# breakout.net
KiCad netlist of a schematic drawn in EAGLE
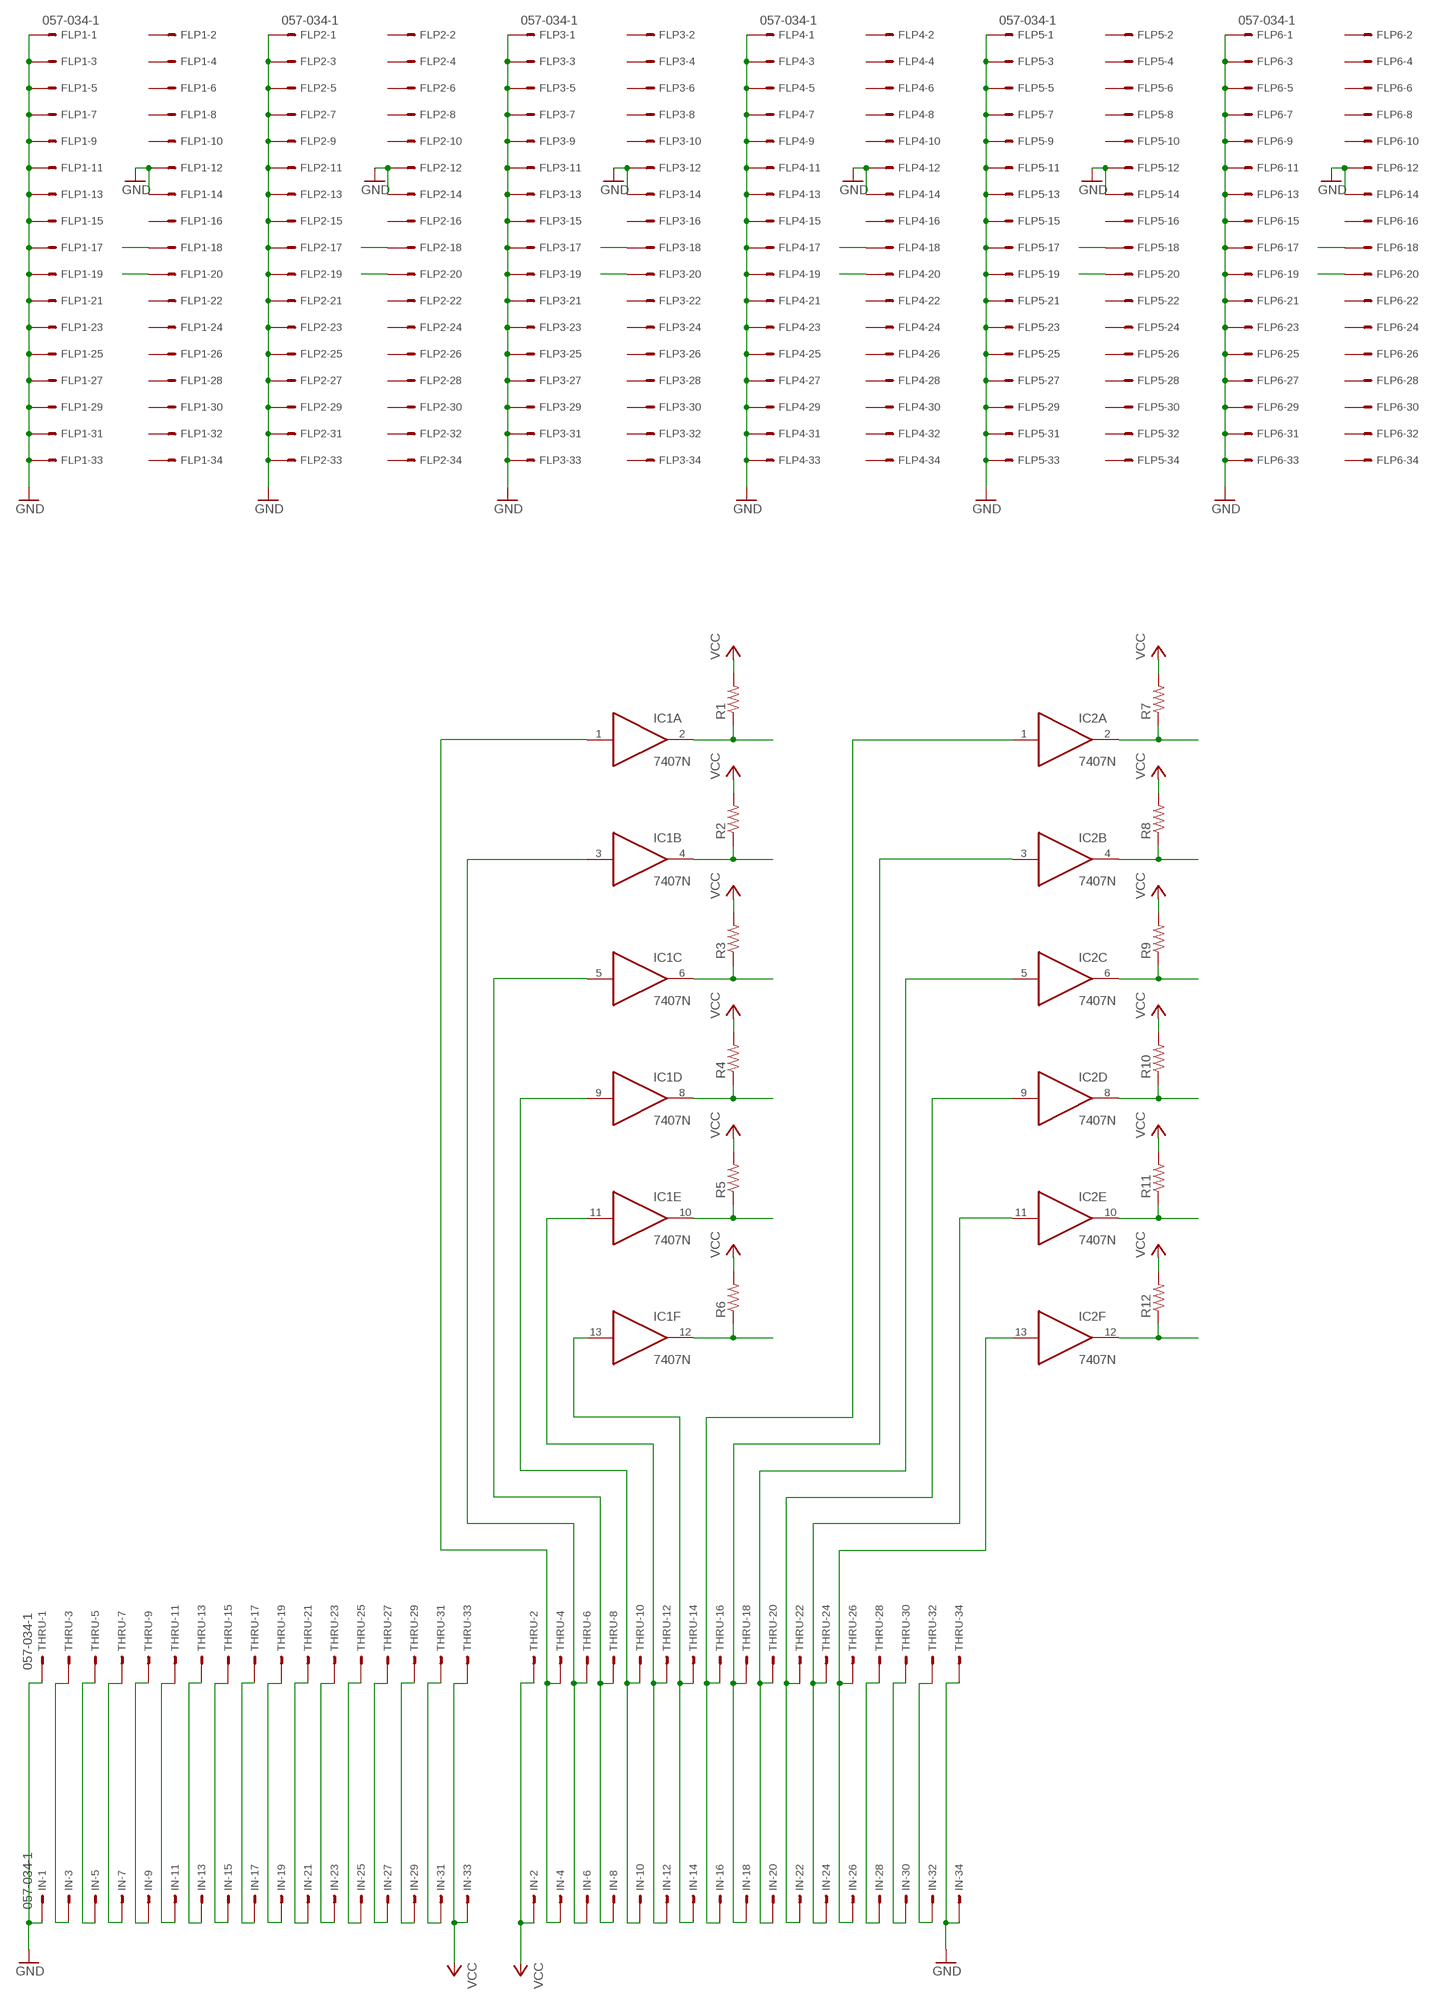
[diagram p0: schematic, sheet 1]

(export (version "E")
  (design (tool "Eeschema 10.0.6"))
  (components
    (comp (ref "FLP1")
      (value "057-034-1")
      (footprint "eagle-import:057-034-1")
      (libsource (lib "eagle-import") (part "057-034-1"))
    )
    (comp (ref "FLP2")
      (value "057-034-1")
      (footprint "eagle-import:057-034-1")
      (libsource (lib "eagle-import") (part "057-034-1"))
    )
    (comp (ref "FLP3")
      (value "057-034-1")
      (footprint "eagle-import:057-034-1")
      (libsource (lib "eagle-import") (part "057-034-1"))
    )
    (comp (ref "FLP4")
      (value "057-034-1")
      (footprint "eagle-import:057-034-1")
      (libsource (lib "eagle-import") (part "057-034-1"))
    )
    (comp (ref "FLP5")
      (value "057-034-1")
      (footprint "eagle-import:057-034-1")
      (libsource (lib "eagle-import") (part "057-034-1"))
    )
    (comp (ref "FLP6")
      (value "057-034-1")
      (footprint "eagle-import:057-034-1")
      (libsource (lib "eagle-import") (part "057-034-1"))
    )
    (comp (ref "IC1")
      (value "7407N")
      (footprint "eagle-import:DIL14")
      (libsource (lib "eagle-import") (part "7407N"))
    )
    (comp (ref "IC2")
      (value "7407N")
      (footprint "eagle-import:DIL14")
      (libsource (lib "eagle-import") (part "7407N"))
    )
    (comp (ref "IN")
      (value "057-034-1")
      (footprint "eagle-import:057-034-1")
      (libsource (lib "eagle-import") (part "057-034-1"))
    )
    (comp (ref "R1")
      (value "R-US_0204/7")
      (footprint "eagle-import:0204_7")
      (libsource (lib "eagle-import") (part "R-US_0204/7"))
    )
    (comp (ref "R2")
      (value "R-US_0204/7")
      (footprint "eagle-import:0204_7")
      (libsource (lib "eagle-import") (part "R-US_0204/7"))
    )
    (comp (ref "R3")
      (value "R-US_0204/7")
      (footprint "eagle-import:0204_7")
      (libsource (lib "eagle-import") (part "R-US_0204/7"))
    )
    (comp (ref "R4")
      (value "R-US_0204/7")
      (footprint "eagle-import:0204_7")
      (libsource (lib "eagle-import") (part "R-US_0204/7"))
    )
    (comp (ref "R5")
      (value "R-US_0204/7")
      (footprint "eagle-import:0204_7")
      (libsource (lib "eagle-import") (part "R-US_0204/7"))
    )
    (comp (ref "R6")
      (value "R-US_0204/7")
      (footprint "eagle-import:0204_7")
      (libsource (lib "eagle-import") (part "R-US_0204/7"))
    )
    (comp (ref "R7")
      (value "R-US_0204/7")
      (footprint "eagle-import:0204_7")
      (libsource (lib "eagle-import") (part "R-US_0204/7"))
    )
    (comp (ref "R8")
      (value "R-US_0204/7")
      (footprint "eagle-import:0204_7")
      (libsource (lib "eagle-import") (part "R-US_0204/7"))
    )
    (comp (ref "R9")
      (value "R-US_0204/7")
      (footprint "eagle-import:0204_7")
      (libsource (lib "eagle-import") (part "R-US_0204/7"))
    )
    (comp (ref "R10")
      (value "R-US_0204/7")
      (footprint "eagle-import:0204_7")
      (libsource (lib "eagle-import") (part "R-US_0204/7"))
    )
    (comp (ref "R11")
      (value "R-US_0204/7")
      (footprint "eagle-import:0204_7")
      (libsource (lib "eagle-import") (part "R-US_0204/7"))
    )
    (comp (ref "R12")
      (value "R-US_0204/7")
      (footprint "eagle-import:0204_7")
      (libsource (lib "eagle-import") (part "R-US_0204/7"))
    )
    (comp (ref "THRU")
      (value "057-034-1")
      (footprint "eagle-import:057-034-1")
      (libsource (lib "eagle-import") (part "057-034-1"))
    )
  )
  (nets
    (net (code "1") (name "/DIRECTION_1") (class "Default")
      (node (ref "FLP1") (pin "18") (pinfunction "S_18") (pintype "passive"))
      (node (ref "IC1") (pin "2") (pinfunction "O_2") (pintype "open_collector"))
      (node (ref "R1") (pin "1") (pinfunction "1_1") (pintype "passive"))
    )
    (net (code "2") (name "/DIRECTION_2") (class "Default")
      (node (ref "FLP2") (pin "18") (pinfunction "S_18") (pintype "passive"))
      (node (ref "IC1") (pin "6") (pinfunction "O_6") (pintype "open_collector"))
      (node (ref "R3") (pin "1") (pinfunction "1_1") (pintype "passive"))
    )
    (net (code "3") (name "/DIRECTION_3") (class "Default")
      (node (ref "FLP3") (pin "18") (pinfunction "S_18") (pintype "passive"))
      (node (ref "IC1") (pin "10") (pinfunction "O_10") (pintype "open_collector"))
      (node (ref "R5") (pin "1") (pinfunction "1_1") (pintype "passive"))
    )
    (net (code "4") (name "/DIRECTION_4") (class "Default")
      (node (ref "FLP4") (pin "18") (pinfunction "S_18") (pintype "passive"))
      (node (ref "IC2") (pin "2") (pinfunction "O_2") (pintype "open_collector"))
      (node (ref "R7") (pin "1") (pinfunction "1_1") (pintype "passive"))
    )
    (net (code "5") (name "/DIRECTION_5") (class "Default")
      (node (ref "FLP5") (pin "18") (pinfunction "S_18") (pintype "passive"))
      (node (ref "IC2") (pin "6") (pinfunction "O_6") (pintype "open_collector"))
      (node (ref "R9") (pin "1") (pinfunction "1_1") (pintype "passive"))
    )
    (net (code "6") (name "/DIRECTION_6") (class "Default")
      (node (ref "FLP6") (pin "18") (pinfunction "S_18") (pintype "passive"))
      (node (ref "IC2") (pin "10") (pinfunction "O_10") (pintype "open_collector"))
      (node (ref "R11") (pin "1") (pinfunction "1_1") (pintype "passive"))
    )
    (net (code "7") (name "/STEP_1") (class "Default")
      (node (ref "FLP1") (pin "20") (pinfunction "S_20") (pintype "passive"))
      (node (ref "IC1") (pin "4") (pinfunction "O_4") (pintype "open_collector"))
      (node (ref "R2") (pin "1") (pinfunction "1_1") (pintype "passive"))
    )
    (net (code "8") (name "/STEP_2") (class "Default")
      (node (ref "FLP2") (pin "20") (pinfunction "S_20") (pintype "passive"))
      (node (ref "IC1") (pin "8") (pinfunction "O_8") (pintype "open_collector"))
      (node (ref "R4") (pin "1") (pinfunction "1_1") (pintype "passive"))
    )
    (net (code "9") (name "/STEP_3") (class "Default")
      (node (ref "FLP3") (pin "20") (pinfunction "S_20") (pintype "passive"))
      (node (ref "IC1") (pin "12") (pinfunction "O_12") (pintype "open_collector"))
      (node (ref "R6") (pin "1") (pinfunction "1_1") (pintype "passive"))
    )
    (net (code "10") (name "/STEP_4") (class "Default")
      (node (ref "FLP4") (pin "20") (pinfunction "S_20") (pintype "passive"))
      (node (ref "IC2") (pin "4") (pinfunction "O_4") (pintype "open_collector"))
      (node (ref "R8") (pin "1") (pinfunction "1_1") (pintype "passive"))
    )
    (net (code "11") (name "/STEP_5") (class "Default")
      (node (ref "FLP5") (pin "20") (pinfunction "S_20") (pintype "passive"))
      (node (ref "IC2") (pin "8") (pinfunction "O_8") (pintype "open_collector"))
      (node (ref "R10") (pin "1") (pinfunction "1_1") (pintype "passive"))
    )
    (net (code "12") (name "/STEP_6") (class "Default")
      (node (ref "FLP6") (pin "20") (pinfunction "S_20") (pintype "passive"))
      (node (ref "IC2") (pin "12") (pinfunction "O_12") (pintype "open_collector"))
      (node (ref "R12") (pin "1") (pinfunction "1_1") (pintype "passive"))
    )
    (net (code "13") (name "GND") (class "Default")
      (node (ref "FLP1") (pin "1") (pinfunction "S_1") (pintype "passive"))
      (node (ref "FLP1") (pin "11") (pinfunction "S_11") (pintype "passive"))
      (node (ref "FLP1") (pin "12") (pinfunction "S_12") (pintype "passive"))
      (node (ref "FLP1") (pin "13") (pinfunction "S_13") (pintype "passive"))
      (node (ref "FLP1") (pin "14") (pinfunction "S_14") (pintype "passive"))
      (node (ref "FLP1") (pin "15") (pinfunction "S_15") (pintype "passive"))
      (node (ref "FLP1") (pin "17") (pinfunction "S_17") (pintype "passive"))
      (node (ref "FLP1") (pin "19") (pinfunction "S_19") (pintype "passive"))
      (node (ref "FLP1") (pin "21") (pinfunction "S_21") (pintype "passive"))
      (node (ref "FLP1") (pin "23") (pinfunction "S_23") (pintype "passive"))
      (node (ref "FLP1") (pin "25") (pinfunction "S_25") (pintype "passive"))
      (node (ref "FLP1") (pin "27") (pinfunction "S_27") (pintype "passive"))
      (node (ref "FLP1") (pin "29") (pinfunction "S_29") (pintype "passive"))
      (node (ref "FLP1") (pin "3") (pinfunction "S_3") (pintype "passive"))
      (node (ref "FLP1") (pin "31") (pinfunction "S_31") (pintype "passive"))
      (node (ref "FLP1") (pin "33") (pinfunction "S_33") (pintype "passive"))
      (node (ref "FLP1") (pin "5") (pinfunction "S_5") (pintype "passive"))
      (node (ref "FLP1") (pin "7") (pinfunction "S_7") (pintype "passive"))
      (node (ref "FLP1") (pin "9") (pinfunction "S_9") (pintype "passive"))
      (node (ref "FLP2") (pin "1") (pinfunction "S_1") (pintype "passive"))
      (node (ref "FLP2") (pin "11") (pinfunction "S_11") (pintype "passive"))
      (node (ref "FLP2") (pin "12") (pinfunction "S_12") (pintype "passive"))
      (node (ref "FLP2") (pin "13") (pinfunction "S_13") (pintype "passive"))
      (node (ref "FLP2") (pin "14") (pinfunction "S_14") (pintype "passive"))
      (node (ref "FLP2") (pin "15") (pinfunction "S_15") (pintype "passive"))
      (node (ref "FLP2") (pin "17") (pinfunction "S_17") (pintype "passive"))
      (node (ref "FLP2") (pin "19") (pinfunction "S_19") (pintype "passive"))
      (node (ref "FLP2") (pin "21") (pinfunction "S_21") (pintype "passive"))
      (node (ref "FLP2") (pin "23") (pinfunction "S_23") (pintype "passive"))
      (node (ref "FLP2") (pin "25") (pinfunction "S_25") (pintype "passive"))
      (node (ref "FLP2") (pin "27") (pinfunction "S_27") (pintype "passive"))
      (node (ref "FLP2") (pin "29") (pinfunction "S_29") (pintype "passive"))
      (node (ref "FLP2") (pin "3") (pinfunction "S_3") (pintype "passive"))
      (node (ref "FLP2") (pin "31") (pinfunction "S_31") (pintype "passive"))
      (node (ref "FLP2") (pin "33") (pinfunction "S_33") (pintype "passive"))
      (node (ref "FLP2") (pin "5") (pinfunction "S_5") (pintype "passive"))
      (node (ref "FLP2") (pin "7") (pinfunction "S_7") (pintype "passive"))
      (node (ref "FLP2") (pin "9") (pinfunction "S_9") (pintype "passive"))
      (node (ref "FLP3") (pin "1") (pinfunction "S_1") (pintype "passive"))
      (node (ref "FLP3") (pin "11") (pinfunction "S_11") (pintype "passive"))
      (node (ref "FLP3") (pin "12") (pinfunction "S_12") (pintype "passive"))
      (node (ref "FLP3") (pin "13") (pinfunction "S_13") (pintype "passive"))
      (node (ref "FLP3") (pin "14") (pinfunction "S_14") (pintype "passive"))
      (node (ref "FLP3") (pin "15") (pinfunction "S_15") (pintype "passive"))
      (node (ref "FLP3") (pin "17") (pinfunction "S_17") (pintype "passive"))
      (node (ref "FLP3") (pin "19") (pinfunction "S_19") (pintype "passive"))
      (node (ref "FLP3") (pin "21") (pinfunction "S_21") (pintype "passive"))
      (node (ref "FLP3") (pin "23") (pinfunction "S_23") (pintype "passive"))
      (node (ref "FLP3") (pin "25") (pinfunction "S_25") (pintype "passive"))
      (node (ref "FLP3") (pin "27") (pinfunction "S_27") (pintype "passive"))
      (node (ref "FLP3") (pin "29") (pinfunction "S_29") (pintype "passive"))
      (node (ref "FLP3") (pin "3") (pinfunction "S_3") (pintype "passive"))
      (node (ref "FLP3") (pin "31") (pinfunction "S_31") (pintype "passive"))
      (node (ref "FLP3") (pin "33") (pinfunction "S_33") (pintype "passive"))
      (node (ref "FLP3") (pin "5") (pinfunction "S_5") (pintype "passive"))
      (node (ref "FLP3") (pin "7") (pinfunction "S_7") (pintype "passive"))
      (node (ref "FLP3") (pin "9") (pinfunction "S_9") (pintype "passive"))
      (node (ref "FLP4") (pin "1") (pinfunction "S_1") (pintype "passive"))
      (node (ref "FLP4") (pin "11") (pinfunction "S_11") (pintype "passive"))
      (node (ref "FLP4") (pin "12") (pinfunction "S_12") (pintype "passive"))
      (node (ref "FLP4") (pin "13") (pinfunction "S_13") (pintype "passive"))
      (node (ref "FLP4") (pin "14") (pinfunction "S_14") (pintype "passive"))
      (node (ref "FLP4") (pin "15") (pinfunction "S_15") (pintype "passive"))
      (node (ref "FLP4") (pin "17") (pinfunction "S_17") (pintype "passive"))
      (node (ref "FLP4") (pin "19") (pinfunction "S_19") (pintype "passive"))
      (node (ref "FLP4") (pin "21") (pinfunction "S_21") (pintype "passive"))
      (node (ref "FLP4") (pin "23") (pinfunction "S_23") (pintype "passive"))
      (node (ref "FLP4") (pin "25") (pinfunction "S_25") (pintype "passive"))
      (node (ref "FLP4") (pin "27") (pinfunction "S_27") (pintype "passive"))
      (node (ref "FLP4") (pin "29") (pinfunction "S_29") (pintype "passive"))
      (node (ref "FLP4") (pin "3") (pinfunction "S_3") (pintype "passive"))
      (node (ref "FLP4") (pin "31") (pinfunction "S_31") (pintype "passive"))
      (node (ref "FLP4") (pin "33") (pinfunction "S_33") (pintype "passive"))
      (node (ref "FLP4") (pin "5") (pinfunction "S_5") (pintype "passive"))
      (node (ref "FLP4") (pin "7") (pinfunction "S_7") (pintype "passive"))
      (node (ref "FLP4") (pin "9") (pinfunction "S_9") (pintype "passive"))
      (node (ref "FLP5") (pin "1") (pinfunction "S_1") (pintype "passive"))
      (node (ref "FLP5") (pin "11") (pinfunction "S_11") (pintype "passive"))
      (node (ref "FLP5") (pin "12") (pinfunction "S_12") (pintype "passive"))
      (node (ref "FLP5") (pin "13") (pinfunction "S_13") (pintype "passive"))
      (node (ref "FLP5") (pin "14") (pinfunction "S_14") (pintype "passive"))
      (node (ref "FLP5") (pin "15") (pinfunction "S_15") (pintype "passive"))
      (node (ref "FLP5") (pin "17") (pinfunction "S_17") (pintype "passive"))
      (node (ref "FLP5") (pin "19") (pinfunction "S_19") (pintype "passive"))
      (node (ref "FLP5") (pin "21") (pinfunction "S_21") (pintype "passive"))
      (node (ref "FLP5") (pin "23") (pinfunction "S_23") (pintype "passive"))
      (node (ref "FLP5") (pin "25") (pinfunction "S_25") (pintype "passive"))
      (node (ref "FLP5") (pin "27") (pinfunction "S_27") (pintype "passive"))
      (node (ref "FLP5") (pin "29") (pinfunction "S_29") (pintype "passive"))
      (node (ref "FLP5") (pin "3") (pinfunction "S_3") (pintype "passive"))
      (node (ref "FLP5") (pin "31") (pinfunction "S_31") (pintype "passive"))
      (node (ref "FLP5") (pin "33") (pinfunction "S_33") (pintype "passive"))
      (node (ref "FLP5") (pin "5") (pinfunction "S_5") (pintype "passive"))
      (node (ref "FLP5") (pin "7") (pinfunction "S_7") (pintype "passive"))
      (node (ref "FLP5") (pin "9") (pinfunction "S_9") (pintype "passive"))
      (node (ref "FLP6") (pin "1") (pinfunction "S_1") (pintype "passive"))
      (node (ref "FLP6") (pin "11") (pinfunction "S_11") (pintype "passive"))
      (node (ref "FLP6") (pin "12") (pinfunction "S_12") (pintype "passive"))
      (node (ref "FLP6") (pin "13") (pinfunction "S_13") (pintype "passive"))
      (node (ref "FLP6") (pin "14") (pinfunction "S_14") (pintype "passive"))
      (node (ref "FLP6") (pin "15") (pinfunction "S_15") (pintype "passive"))
      (node (ref "FLP6") (pin "17") (pinfunction "S_17") (pintype "passive"))
      (node (ref "FLP6") (pin "19") (pinfunction "S_19") (pintype "passive"))
      (node (ref "FLP6") (pin "21") (pinfunction "S_21") (pintype "passive"))
      (node (ref "FLP6") (pin "23") (pinfunction "S_23") (pintype "passive"))
      (node (ref "FLP6") (pin "25") (pinfunction "S_25") (pintype "passive"))
      (node (ref "FLP6") (pin "27") (pinfunction "S_27") (pintype "passive"))
      (node (ref "FLP6") (pin "29") (pinfunction "S_29") (pintype "passive"))
      (node (ref "FLP6") (pin "3") (pinfunction "S_3") (pintype "passive"))
      (node (ref "FLP6") (pin "31") (pinfunction "S_31") (pintype "passive"))
      (node (ref "FLP6") (pin "33") (pinfunction "S_33") (pintype "passive"))
      (node (ref "FLP6") (pin "5") (pinfunction "S_5") (pintype "passive"))
      (node (ref "FLP6") (pin "7") (pinfunction "S_7") (pintype "passive"))
      (node (ref "FLP6") (pin "9") (pinfunction "S_9") (pintype "passive"))
      (node (ref "IN") (pin "1") (pinfunction "S_1") (pintype "passive"))
      (node (ref "IN") (pin "34") (pinfunction "S_34") (pintype "passive"))
      (node (ref "THRU") (pin "1") (pinfunction "S_1") (pintype "passive"))
      (node (ref "THRU") (pin "34") (pinfunction "S_34") (pintype "passive"))
    )
    (net (code "14") (name "Net-(IC1A-I)") (class "Default")
      (node (ref "IC1") (pin "1") (pinfunction "I_1") (pintype "input"))
      (node (ref "IN") (pin "4") (pinfunction "S_4") (pintype "passive"))
      (node (ref "THRU") (pin "4") (pinfunction "S_4") (pintype "passive"))
    )
    (net (code "15") (name "Net-(IC1B-I)") (class "Default")
      (node (ref "IC1") (pin "3") (pinfunction "I_3") (pintype "input"))
      (node (ref "IN") (pin "6") (pinfunction "S_6") (pintype "passive"))
      (node (ref "THRU") (pin "6") (pinfunction "S_6") (pintype "passive"))
    )
    (net (code "16") (name "Net-(IC1C-I)") (class "Default")
      (node (ref "IC1") (pin "5") (pinfunction "I_5") (pintype "input"))
      (node (ref "IN") (pin "8") (pinfunction "S_8") (pintype "passive"))
      (node (ref "THRU") (pin "8") (pinfunction "S_8") (pintype "passive"))
    )
    (net (code "17") (name "Net-(IC1D-I)") (class "Default")
      (node (ref "IC1") (pin "9") (pinfunction "I_9") (pintype "input"))
      (node (ref "IN") (pin "10") (pinfunction "S_10") (pintype "passive"))
      (node (ref "THRU") (pin "10") (pinfunction "S_10") (pintype "passive"))
    )
    (net (code "18") (name "Net-(IC1E-I)") (class "Default")
      (node (ref "IC1") (pin "11") (pinfunction "I_11") (pintype "input"))
      (node (ref "IN") (pin "12") (pinfunction "S_12") (pintype "passive"))
      (node (ref "THRU") (pin "12") (pinfunction "S_12") (pintype "passive"))
    )
    (net (code "19") (name "Net-(IC1F-I)") (class "Default")
      (node (ref "IC1") (pin "13") (pinfunction "I_13") (pintype "input"))
      (node (ref "IN") (pin "14") (pinfunction "S_14") (pintype "passive"))
      (node (ref "THRU") (pin "14") (pinfunction "S_14") (pintype "passive"))
    )
    (net (code "20") (name "Net-(IC2A-I)") (class "Default")
      (node (ref "IC2") (pin "1") (pinfunction "I_1") (pintype "input"))
      (node (ref "IN") (pin "16") (pinfunction "S_16") (pintype "passive"))
      (node (ref "THRU") (pin "16") (pinfunction "S_16") (pintype "passive"))
    )
    (net (code "21") (name "Net-(IC2B-I)") (class "Default")
      (node (ref "IC2") (pin "3") (pinfunction "I_3") (pintype "input"))
      (node (ref "IN") (pin "18") (pinfunction "S_18") (pintype "passive"))
      (node (ref "THRU") (pin "18") (pinfunction "S_18") (pintype "passive"))
    )
    (net (code "22") (name "Net-(IC2C-I)") (class "Default")
      (node (ref "IC2") (pin "5") (pinfunction "I_5") (pintype "input"))
      (node (ref "IN") (pin "20") (pinfunction "S_20") (pintype "passive"))
      (node (ref "THRU") (pin "20") (pinfunction "S_20") (pintype "passive"))
    )
    (net (code "23") (name "Net-(IC2D-I)") (class "Default")
      (node (ref "IC2") (pin "9") (pinfunction "I_9") (pintype "input"))
      (node (ref "IN") (pin "22") (pinfunction "S_22") (pintype "passive"))
      (node (ref "THRU") (pin "22") (pinfunction "S_22") (pintype "passive"))
    )
    (net (code "24") (name "Net-(IC2E-I)") (class "Default")
      (node (ref "IC2") (pin "11") (pinfunction "I_11") (pintype "input"))
      (node (ref "IN") (pin "24") (pinfunction "S_24") (pintype "passive"))
      (node (ref "THRU") (pin "24") (pinfunction "S_24") (pintype "passive"))
    )
    (net (code "25") (name "Net-(IC2F-I)") (class "Default")
      (node (ref "IC2") (pin "13") (pinfunction "I_13") (pintype "input"))
      (node (ref "IN") (pin "26") (pinfunction "S_26") (pintype "passive"))
      (node (ref "THRU") (pin "26") (pinfunction "S_26") (pintype "passive"))
    )
    (net (code "26") (name "Net-(INAD-S)") (class "Default")
      (node (ref "IN") (pin "5") (pinfunction "S_5") (pintype "passive"))
      (node (ref "THRU") (pin "5") (pinfunction "S_5") (pintype "passive"))
    )
    (net (code "27") (name "Net-(INAF-S)") (class "Default")
      (node (ref "IN") (pin "7") (pinfunction "S_7") (pintype "passive"))
      (node (ref "THRU") (pin "7") (pinfunction "S_7") (pintype "passive"))
    )
    (net (code "28") (name "Net-(INAH-S)") (class "Default")
      (node (ref "IN") (pin "9") (pinfunction "S_9") (pintype "passive"))
      (node (ref "THRU") (pin "9") (pinfunction "S_9") (pintype "passive"))
    )
    (net (code "29") (name "Net-(INC-S)") (class "Default")
      (node (ref "IN") (pin "11") (pinfunction "S_11") (pintype "passive"))
      (node (ref "THRU") (pin "11") (pinfunction "S_11") (pintype "passive"))
    )
    (net (code "30") (name "Net-(INE-S)") (class "Default")
      (node (ref "IN") (pin "13") (pinfunction "S_13") (pintype "passive"))
      (node (ref "THRU") (pin "13") (pinfunction "S_13") (pintype "passive"))
    )
    (net (code "31") (name "Net-(ING-S)") (class "Default")
      (node (ref "IN") (pin "15") (pinfunction "S_15") (pintype "passive"))
      (node (ref "THRU") (pin "15") (pinfunction "S_15") (pintype "passive"))
    )
    (net (code "32") (name "Net-(INI-S)") (class "Default")
      (node (ref "IN") (pin "17") (pinfunction "S_17") (pintype "passive"))
      (node (ref "THRU") (pin "17") (pinfunction "S_17") (pintype "passive"))
    )
    (net (code "33") (name "Net-(INK-S)") (class "Default")
      (node (ref "IN") (pin "19") (pinfunction "S_19") (pintype "passive"))
      (node (ref "THRU") (pin "19") (pinfunction "S_19") (pintype "passive"))
    )
    (net (code "34") (name "Net-(INN-S)") (class "Default")
      (node (ref "IN") (pin "21") (pinfunction "S_21") (pintype "passive"))
      (node (ref "THRU") (pin "21") (pinfunction "S_21") (pintype "passive"))
    )
    (net (code "35") (name "Net-(INP-S)") (class "Default")
      (node (ref "IN") (pin "23") (pinfunction "S_23") (pintype "passive"))
      (node (ref "THRU") (pin "23") (pinfunction "S_23") (pintype "passive"))
    )
    (net (code "36") (name "Net-(INR-S)") (class "Default")
      (node (ref "IN") (pin "25") (pinfunction "S_25") (pintype "passive"))
      (node (ref "THRU") (pin "25") (pinfunction "S_25") (pintype "passive"))
    )
    (net (code "37") (name "Net-(INT-S)") (class "Default")
      (node (ref "IN") (pin "27") (pinfunction "S_27") (pintype "passive"))
      (node (ref "THRU") (pin "27") (pinfunction "S_27") (pintype "passive"))
    )
    (net (code "38") (name "Net-(INU-S)") (class "Default")
      (node (ref "IN") (pin "28") (pinfunction "S_28") (pintype "passive"))
      (node (ref "THRU") (pin "28") (pinfunction "S_28") (pintype "passive"))
    )
    (net (code "39") (name "Net-(INV-S)") (class "Default")
      (node (ref "IN") (pin "29") (pinfunction "S_29") (pintype "passive"))
      (node (ref "THRU") (pin "29") (pinfunction "S_29") (pintype "passive"))
    )
    (net (code "40") (name "Net-(INW-S)") (class "Default")
      (node (ref "IN") (pin "3") (pinfunction "S_3") (pintype "passive"))
      (node (ref "THRU") (pin "3") (pinfunction "S_3") (pintype "passive"))
    )
    (net (code "41") (name "Net-(INX-S)") (class "Default")
      (node (ref "IN") (pin "30") (pinfunction "S_30") (pintype "passive"))
      (node (ref "THRU") (pin "30") (pinfunction "S_30") (pintype "passive"))
    )
    (net (code "42") (name "Net-(INY-S)") (class "Default")
      (node (ref "IN") (pin "31") (pinfunction "S_31") (pintype "passive"))
      (node (ref "THRU") (pin "31") (pinfunction "S_31") (pintype "passive"))
    )
    (net (code "43") (name "Net-(INZ-S)") (class "Default")
      (node (ref "IN") (pin "32") (pinfunction "S_32") (pintype "passive"))
      (node (ref "THRU") (pin "32") (pinfunction "S_32") (pintype "passive"))
    )
    (net (code "44") (name "VCC") (class "Default")
      (node (ref "IN") (pin "2") (pinfunction "S_2") (pintype "passive"))
      (node (ref "IN") (pin "33") (pinfunction "S_33") (pintype "passive"))
      (node (ref "R1") (pin "2") (pinfunction "2_2") (pintype "passive"))
      (node (ref "R10") (pin "2") (pinfunction "2_2") (pintype "passive"))
      (node (ref "R11") (pin "2") (pinfunction "2_2") (pintype "passive"))
      (node (ref "R12") (pin "2") (pinfunction "2_2") (pintype "passive"))
      (node (ref "R2") (pin "2") (pinfunction "2_2") (pintype "passive"))
      (node (ref "R3") (pin "2") (pinfunction "2_2") (pintype "passive"))
      (node (ref "R4") (pin "2") (pinfunction "2_2") (pintype "passive"))
      (node (ref "R5") (pin "2") (pinfunction "2_2") (pintype "passive"))
      (node (ref "R6") (pin "2") (pinfunction "2_2") (pintype "passive"))
      (node (ref "R7") (pin "2") (pinfunction "2_2") (pintype "passive"))
      (node (ref "R8") (pin "2") (pinfunction "2_2") (pintype "passive"))
      (node (ref "R9") (pin "2") (pinfunction "2_2") (pintype "passive"))
      (node (ref "THRU") (pin "2") (pinfunction "S_2") (pintype "passive"))
      (node (ref "THRU") (pin "33") (pinfunction "S_33") (pintype "passive"))
    )
    (net (code "45") (name "unconnected-(FLP1AB-S-Pad34)") (class "Default")
      (node (ref "FLP1") (pin "34") (pinfunction "S_34") (pintype "passive"))
    )
    (net (code "46") (name "unconnected-(FLP1AC-S-Pad4)") (class "Default")
      (node (ref "FLP1") (pin "4") (pinfunction "S_4") (pintype "passive"))
    )
    (net (code "47") (name "unconnected-(FLP1AE-S-Pad6)") (class "Default")
      (node (ref "FLP1") (pin "6") (pinfunction "S_6") (pintype "passive"))
    )
    (net (code "48") (name "unconnected-(FLP1AG-S-Pad8)") (class "Default")
      (node (ref "FLP1") (pin "8") (pinfunction "S_8") (pintype "passive"))
    )
    (net (code "49") (name "unconnected-(FLP1B-S-Pad10)") (class "Default")
      (node (ref "FLP1") (pin "10") (pinfunction "S_10") (pintype "passive"))
    )
    (net (code "50") (name "unconnected-(FLP1H-S-Pad16)") (class "Default")
      (node (ref "FLP1") (pin "16") (pinfunction "S_16") (pintype "passive"))
    )
    (net (code "51") (name "unconnected-(FLP1L-S-Pad2)") (class "Default")
      (node (ref "FLP1") (pin "2") (pinfunction "S_2") (pintype "passive"))
    )
    (net (code "52") (name "unconnected-(FLP1O-S-Pad22)") (class "Default")
      (node (ref "FLP1") (pin "22") (pinfunction "S_22") (pintype "passive"))
    )
    (net (code "53") (name "unconnected-(FLP1Q-S-Pad24)") (class "Default")
      (node (ref "FLP1") (pin "24") (pinfunction "S_24") (pintype "passive"))
    )
    (net (code "54") (name "unconnected-(FLP1S-S-Pad26)") (class "Default")
      (node (ref "FLP1") (pin "26") (pinfunction "S_26") (pintype "passive"))
    )
    (net (code "55") (name "unconnected-(FLP1U-S-Pad28)") (class "Default")
      (node (ref "FLP1") (pin "28") (pinfunction "S_28") (pintype "passive"))
    )
    (net (code "56") (name "unconnected-(FLP1X-S-Pad30)") (class "Default")
      (node (ref "FLP1") (pin "30") (pinfunction "S_30") (pintype "passive"))
    )
    (net (code "57") (name "unconnected-(FLP1Z-S-Pad32)") (class "Default")
      (node (ref "FLP1") (pin "32") (pinfunction "S_32") (pintype "passive"))
    )
    (net (code "58") (name "unconnected-(FLP2AB-S-Pad34)") (class "Default")
      (node (ref "FLP2") (pin "34") (pinfunction "S_34") (pintype "passive"))
    )
    (net (code "59") (name "unconnected-(FLP2AC-S-Pad4)") (class "Default")
      (node (ref "FLP2") (pin "4") (pinfunction "S_4") (pintype "passive"))
    )
    (net (code "60") (name "unconnected-(FLP2AE-S-Pad6)") (class "Default")
      (node (ref "FLP2") (pin "6") (pinfunction "S_6") (pintype "passive"))
    )
    (net (code "61") (name "unconnected-(FLP2AG-S-Pad8)") (class "Default")
      (node (ref "FLP2") (pin "8") (pinfunction "S_8") (pintype "passive"))
    )
    (net (code "62") (name "unconnected-(FLP2B-S-Pad10)") (class "Default")
      (node (ref "FLP2") (pin "10") (pinfunction "S_10") (pintype "passive"))
    )
    (net (code "63") (name "unconnected-(FLP2H-S-Pad16)") (class "Default")
      (node (ref "FLP2") (pin "16") (pinfunction "S_16") (pintype "passive"))
    )
    (net (code "64") (name "unconnected-(FLP2L-S-Pad2)") (class "Default")
      (node (ref "FLP2") (pin "2") (pinfunction "S_2") (pintype "passive"))
    )
    (net (code "65") (name "unconnected-(FLP2O-S-Pad22)") (class "Default")
      (node (ref "FLP2") (pin "22") (pinfunction "S_22") (pintype "passive"))
    )
    (net (code "66") (name "unconnected-(FLP2Q-S-Pad24)") (class "Default")
      (node (ref "FLP2") (pin "24") (pinfunction "S_24") (pintype "passive"))
    )
    (net (code "67") (name "unconnected-(FLP2S-S-Pad26)") (class "Default")
      (node (ref "FLP2") (pin "26") (pinfunction "S_26") (pintype "passive"))
    )
    (net (code "68") (name "unconnected-(FLP2U-S-Pad28)") (class "Default")
      (node (ref "FLP2") (pin "28") (pinfunction "S_28") (pintype "passive"))
    )
    (net (code "69") (name "unconnected-(FLP2X-S-Pad30)") (class "Default")
      (node (ref "FLP2") (pin "30") (pinfunction "S_30") (pintype "passive"))
    )
    (net (code "70") (name "unconnected-(FLP2Z-S-Pad32)") (class "Default")
      (node (ref "FLP2") (pin "32") (pinfunction "S_32") (pintype "passive"))
    )
    (net (code "71") (name "unconnected-(FLP3AB-S-Pad34)") (class "Default")
      (node (ref "FLP3") (pin "34") (pinfunction "S_34") (pintype "passive"))
    )
    (net (code "72") (name "unconnected-(FLP3AC-S-Pad4)") (class "Default")
      (node (ref "FLP3") (pin "4") (pinfunction "S_4") (pintype "passive"))
    )
    (net (code "73") (name "unconnected-(FLP3AE-S-Pad6)") (class "Default")
      (node (ref "FLP3") (pin "6") (pinfunction "S_6") (pintype "passive"))
    )
    (net (code "74") (name "unconnected-(FLP3AG-S-Pad8)") (class "Default")
      (node (ref "FLP3") (pin "8") (pinfunction "S_8") (pintype "passive"))
    )
    (net (code "75") (name "unconnected-(FLP3B-S-Pad10)") (class "Default")
      (node (ref "FLP3") (pin "10") (pinfunction "S_10") (pintype "passive"))
    )
    (net (code "76") (name "unconnected-(FLP3H-S-Pad16)") (class "Default")
      (node (ref "FLP3") (pin "16") (pinfunction "S_16") (pintype "passive"))
    )
    (net (code "77") (name "unconnected-(FLP3L-S-Pad2)") (class "Default")
      (node (ref "FLP3") (pin "2") (pinfunction "S_2") (pintype "passive"))
    )
    (net (code "78") (name "unconnected-(FLP3O-S-Pad22)") (class "Default")
      (node (ref "FLP3") (pin "22") (pinfunction "S_22") (pintype "passive"))
    )
    (net (code "79") (name "unconnected-(FLP3Q-S-Pad24)") (class "Default")
      (node (ref "FLP3") (pin "24") (pinfunction "S_24") (pintype "passive"))
    )
    (net (code "80") (name "unconnected-(FLP3S-S-Pad26)") (class "Default")
      (node (ref "FLP3") (pin "26") (pinfunction "S_26") (pintype "passive"))
    )
    (net (code "81") (name "unconnected-(FLP3U-S-Pad28)") (class "Default")
      (node (ref "FLP3") (pin "28") (pinfunction "S_28") (pintype "passive"))
    )
    (net (code "82") (name "unconnected-(FLP3X-S-Pad30)") (class "Default")
      (node (ref "FLP3") (pin "30") (pinfunction "S_30") (pintype "passive"))
    )
    (net (code "83") (name "unconnected-(FLP3Z-S-Pad32)") (class "Default")
      (node (ref "FLP3") (pin "32") (pinfunction "S_32") (pintype "passive"))
    )
    (net (code "84") (name "unconnected-(FLP4AB-S-Pad34)") (class "Default")
      (node (ref "FLP4") (pin "34") (pinfunction "S_34") (pintype "passive"))
    )
    (net (code "85") (name "unconnected-(FLP4AC-S-Pad4)") (class "Default")
      (node (ref "FLP4") (pin "4") (pinfunction "S_4") (pintype "passive"))
    )
    (net (code "86") (name "unconnected-(FLP4AE-S-Pad6)") (class "Default")
      (node (ref "FLP4") (pin "6") (pinfunction "S_6") (pintype "passive"))
    )
    (net (code "87") (name "unconnected-(FLP4AG-S-Pad8)") (class "Default")
      (node (ref "FLP4") (pin "8") (pinfunction "S_8") (pintype "passive"))
    )
    (net (code "88") (name "unconnected-(FLP4B-S-Pad10)") (class "Default")
      (node (ref "FLP4") (pin "10") (pinfunction "S_10") (pintype "passive"))
    )
    (net (code "89") (name "unconnected-(FLP4H-S-Pad16)") (class "Default")
      (node (ref "FLP4") (pin "16") (pinfunction "S_16") (pintype "passive"))
    )
    (net (code "90") (name "unconnected-(FLP4L-S-Pad2)") (class "Default")
      (node (ref "FLP4") (pin "2") (pinfunction "S_2") (pintype "passive"))
    )
    (net (code "91") (name "unconnected-(FLP4O-S-Pad22)") (class "Default")
      (node (ref "FLP4") (pin "22") (pinfunction "S_22") (pintype "passive"))
    )
    (net (code "92") (name "unconnected-(FLP4Q-S-Pad24)") (class "Default")
      (node (ref "FLP4") (pin "24") (pinfunction "S_24") (pintype "passive"))
    )
    (net (code "93") (name "unconnected-(FLP4S-S-Pad26)") (class "Default")
      (node (ref "FLP4") (pin "26") (pinfunction "S_26") (pintype "passive"))
    )
    (net (code "94") (name "unconnected-(FLP4U-S-Pad28)") (class "Default")
      (node (ref "FLP4") (pin "28") (pinfunction "S_28") (pintype "passive"))
    )
    (net (code "95") (name "unconnected-(FLP4X-S-Pad30)") (class "Default")
      (node (ref "FLP4") (pin "30") (pinfunction "S_30") (pintype "passive"))
    )
    (net (code "96") (name "unconnected-(FLP4Z-S-Pad32)") (class "Default")
      (node (ref "FLP4") (pin "32") (pinfunction "S_32") (pintype "passive"))
    )
    (net (code "97") (name "unconnected-(FLP5AB-S-Pad34)") (class "Default")
      (node (ref "FLP5") (pin "34") (pinfunction "S_34") (pintype "passive"))
    )
    (net (code "98") (name "unconnected-(FLP5AC-S-Pad4)") (class "Default")
      (node (ref "FLP5") (pin "4") (pinfunction "S_4") (pintype "passive"))
    )
    (net (code "99") (name "unconnected-(FLP5AE-S-Pad6)") (class "Default")
      (node (ref "FLP5") (pin "6") (pinfunction "S_6") (pintype "passive"))
    )
    (net (code "100") (name "unconnected-(FLP5AG-S-Pad8)") (class "Default")
      (node (ref "FLP5") (pin "8") (pinfunction "S_8") (pintype "passive"))
    )
    (net (code "101") (name "unconnected-(FLP5B-S-Pad10)") (class "Default")
      (node (ref "FLP5") (pin "10") (pinfunction "S_10") (pintype "passive"))
    )
    (net (code "102") (name "unconnected-(FLP5H-S-Pad16)") (class "Default")
      (node (ref "FLP5") (pin "16") (pinfunction "S_16") (pintype "passive"))
    )
    (net (code "103") (name "unconnected-(FLP5L-S-Pad2)") (class "Default")
      (node (ref "FLP5") (pin "2") (pinfunction "S_2") (pintype "passive"))
    )
    (net (code "104") (name "unconnected-(FLP5O-S-Pad22)") (class "Default")
      (node (ref "FLP5") (pin "22") (pinfunction "S_22") (pintype "passive"))
    )
    (net (code "105") (name "unconnected-(FLP5Q-S-Pad24)") (class "Default")
      (node (ref "FLP5") (pin "24") (pinfunction "S_24") (pintype "passive"))
    )
    (net (code "106") (name "unconnected-(FLP5S-S-Pad26)") (class "Default")
      (node (ref "FLP5") (pin "26") (pinfunction "S_26") (pintype "passive"))
    )
    (net (code "107") (name "unconnected-(FLP5U-S-Pad28)") (class "Default")
      (node (ref "FLP5") (pin "28") (pinfunction "S_28") (pintype "passive"))
    )
    (net (code "108") (name "unconnected-(FLP5X-S-Pad30)") (class "Default")
      (node (ref "FLP5") (pin "30") (pinfunction "S_30") (pintype "passive"))
    )
    (net (code "109") (name "unconnected-(FLP5Z-S-Pad32)") (class "Default")
      (node (ref "FLP5") (pin "32") (pinfunction "S_32") (pintype "passive"))
    )
    (net (code "110") (name "unconnected-(FLP6AB-S-Pad34)") (class "Default")
      (node (ref "FLP6") (pin "34") (pinfunction "S_34") (pintype "passive"))
    )
    (net (code "111") (name "unconnected-(FLP6AC-S-Pad4)") (class "Default")
      (node (ref "FLP6") (pin "4") (pinfunction "S_4") (pintype "passive"))
    )
    (net (code "112") (name "unconnected-(FLP6AE-S-Pad6)") (class "Default")
      (node (ref "FLP6") (pin "6") (pinfunction "S_6") (pintype "passive"))
    )
    (net (code "113") (name "unconnected-(FLP6AG-S-Pad8)") (class "Default")
      (node (ref "FLP6") (pin "8") (pinfunction "S_8") (pintype "passive"))
    )
    (net (code "114") (name "unconnected-(FLP6B-S-Pad10)") (class "Default")
      (node (ref "FLP6") (pin "10") (pinfunction "S_10") (pintype "passive"))
    )
    (net (code "115") (name "unconnected-(FLP6H-S-Pad16)") (class "Default")
      (node (ref "FLP6") (pin "16") (pinfunction "S_16") (pintype "passive"))
    )
    (net (code "116") (name "unconnected-(FLP6L-S-Pad2)") (class "Default")
      (node (ref "FLP6") (pin "2") (pinfunction "S_2") (pintype "passive"))
    )
    (net (code "117") (name "unconnected-(FLP6O-S-Pad22)") (class "Default")
      (node (ref "FLP6") (pin "22") (pinfunction "S_22") (pintype "passive"))
    )
    (net (code "118") (name "unconnected-(FLP6Q-S-Pad24)") (class "Default")
      (node (ref "FLP6") (pin "24") (pinfunction "S_24") (pintype "passive"))
    )
    (net (code "119") (name "unconnected-(FLP6S-S-Pad26)") (class "Default")
      (node (ref "FLP6") (pin "26") (pinfunction "S_26") (pintype "passive"))
    )
    (net (code "120") (name "unconnected-(FLP6U-S-Pad28)") (class "Default")
      (node (ref "FLP6") (pin "28") (pinfunction "S_28") (pintype "passive"))
    )
    (net (code "121") (name "unconnected-(FLP6X-S-Pad30)") (class "Default")
      (node (ref "FLP6") (pin "30") (pinfunction "S_30") (pintype "passive"))
    )
    (net (code "122") (name "unconnected-(FLP6Z-S-Pad32)") (class "Default")
      (node (ref "FLP6") (pin "32") (pinfunction "S_32") (pintype "passive"))
    )
  )
)
